# wisp-6-afe.net
KiCad netlist of a schematic drawn in Altium Designer
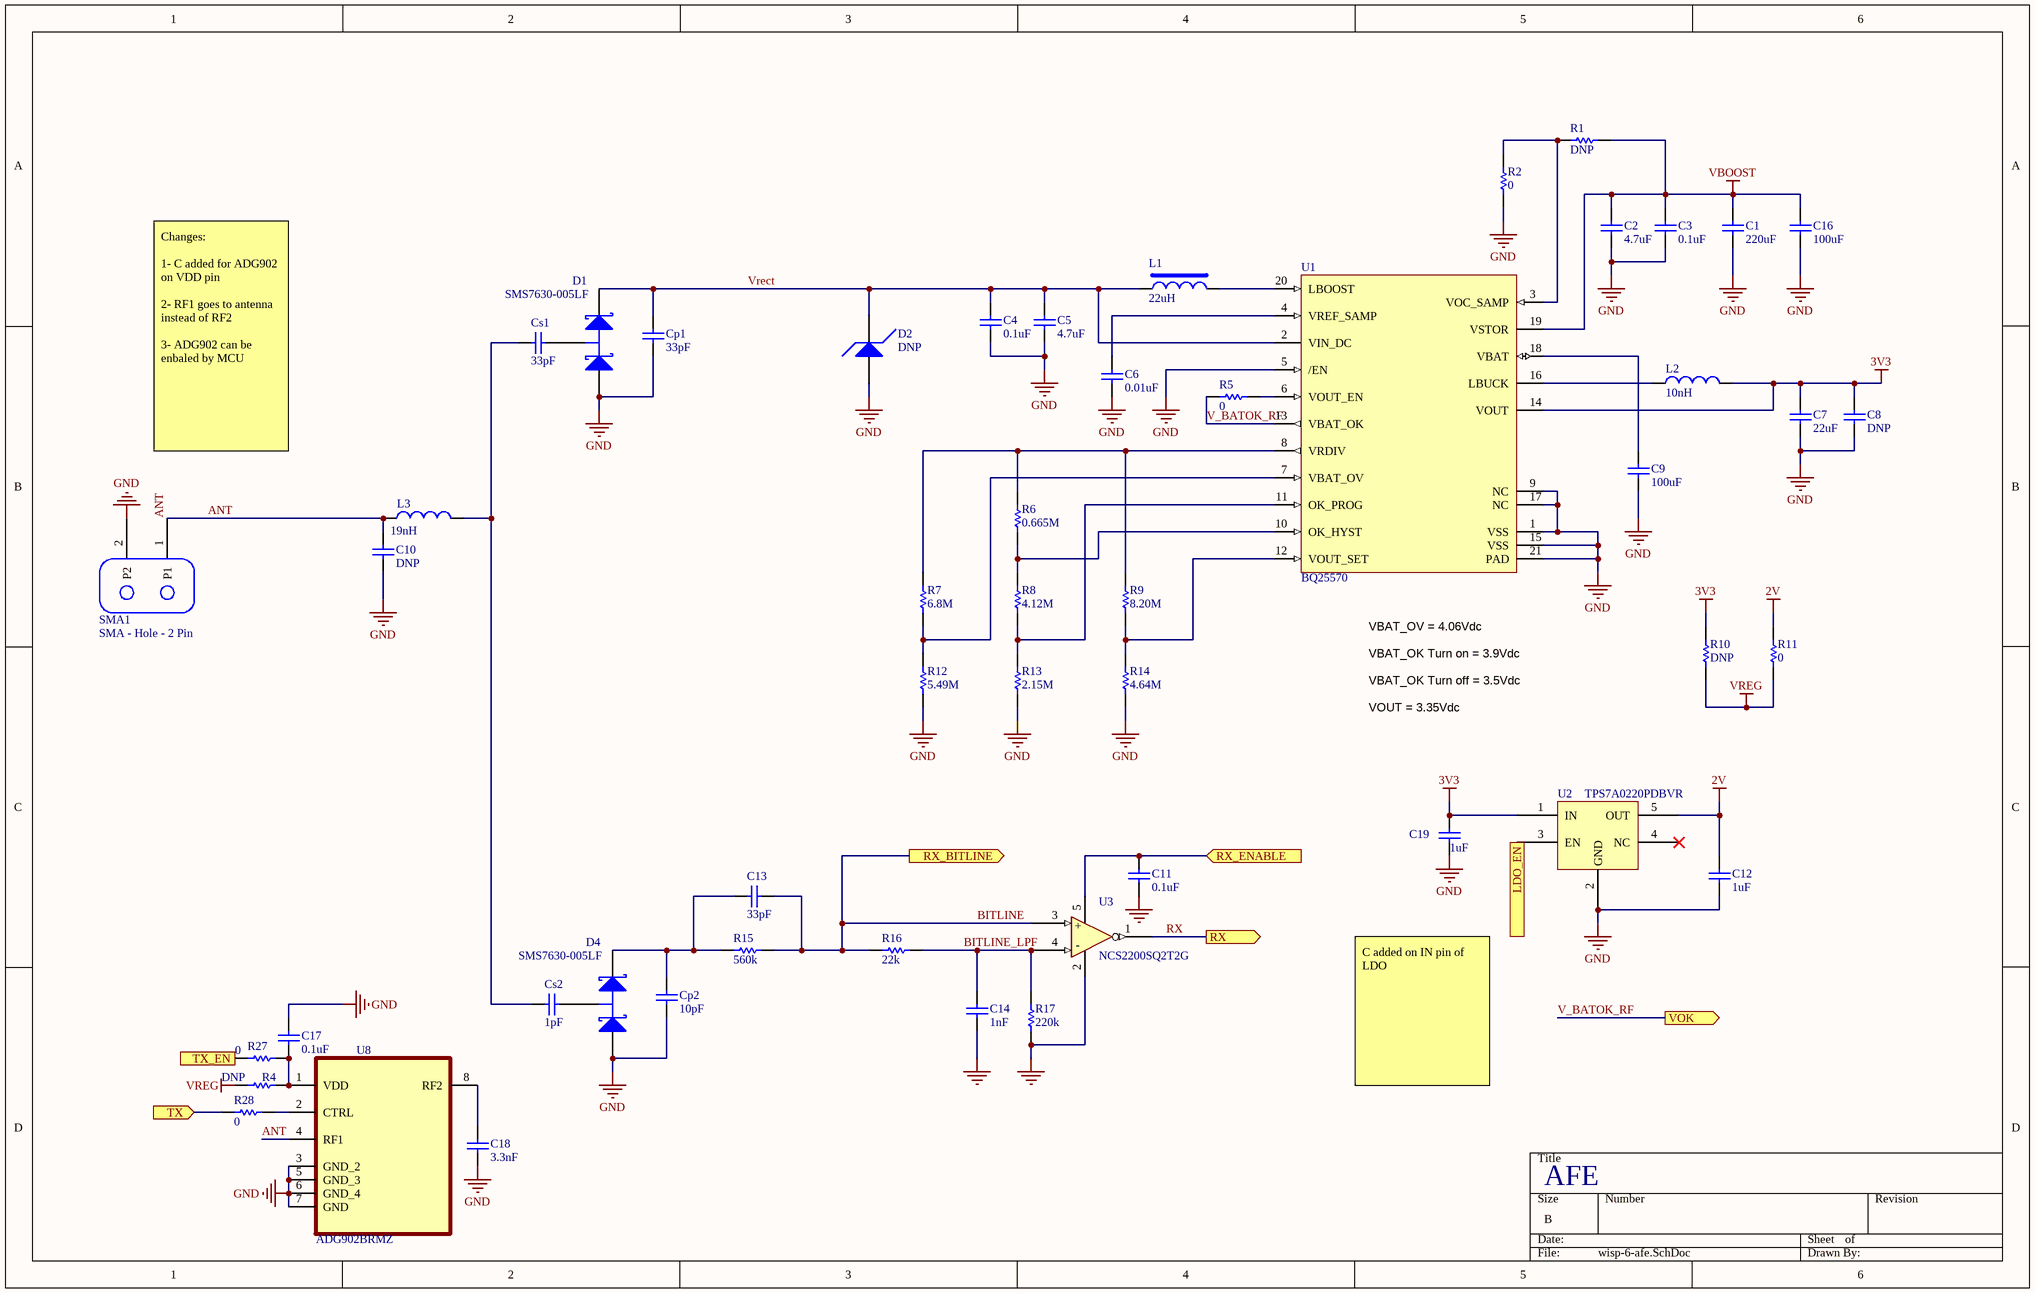
[diagram p0: wisp-6-afe.SchDoc]

(export (version "E")
  (design (tool "Eeschema 10.0.6"))
  (components
    (comp (ref "C1")
      (value "220uF")
      (footprint "1206")
      (description "Ceramic Capacitor (Surface Mount)")
      (fields (field (name "MANUFACTURER") "Generic Ceramic Chip Cap (TBD)") (field (name "Comment") "Cap"))
      (libsource (lib "WISP_AD10") (part "Cap"))
    )
    (comp (ref "C2")
      (value "4.7uF")
      (footprint "0402")
      (description "Ceramic Capacitor (Surface Mount)")
      (fields (field (name "MANUFACTURER") "Generic Ceramic Chip Cap (TBD)") (field (name "Comment") "Cap"))
      (libsource (lib "WISP_AD10") (part "Cap"))
    )
    (comp (ref "C3")
      (value "0.1uF")
      (footprint "0402")
      (description "Ceramic Capacitor (Surface Mount)")
      (fields (field (name "MANUFACTURER") "Generic Ceramic Chip Cap (TBD)") (field (name "Comment") "Cap"))
      (libsource (lib "WISP_AD10") (part "Cap"))
    )
    (comp (ref "C4")
      (value "0.1uF")
      (footprint "0402")
      (description "Ceramic Capacitor (Surface Mount)")
      (fields (field (name "MANUFACTURER") "Generic Ceramic Chip Cap (TBD)") (field (name "Comment") "Cap"))
      (libsource (lib "WISP_AD10") (part "Cap"))
    )
    (comp (ref "C5")
      (value "4.7uF")
      (footprint "0402")
      (description "Ceramic Capacitor (Surface Mount)")
      (fields (field (name "MANUFACTURER") "Generic Ceramic Chip Cap (TBD)") (field (name "Comment") "Cap"))
      (libsource (lib "WISP_AD10") (part "Cap"))
    )
    (comp (ref "C6")
      (value "0.01uF")
      (footprint "0402")
      (description "Ceramic Capacitor (Surface Mount)")
      (fields (field (name "MANUFACTURER") "Generic Ceramic Chip Cap (TBD)") (field (name "Comment") "Cap"))
      (libsource (lib "WISP_AD10") (part "Cap"))
    )
    (comp (ref "C7")
      (value "22uF")
      (footprint "0402")
      (description "Ceramic Capacitor (Surface Mount)")
      (fields (field (name "MANUFACTURER") "Generic Ceramic Chip Cap (TBD)") (field (name "Comment") "Cout1"))
      (libsource (lib "WISP_AD10") (part "Cap"))
    )
    (comp (ref "C8")
      (value "DNP")
      (footprint "0402")
      (description "Ceramic Capacitor (Surface Mount)")
      (fields (field (name "MANUFACTURER") "Generic Ceramic Chip Cap (TBD)") (field (name "Comment") "Cout2"))
      (libsource (lib "WISP_AD10") (part "Cap"))
    )
    (comp (ref "C9")
      (value "100uF")
      (footprint "0805")
      (description "Ceramic Capacitor (Surface Mount)")
      (fields (field (name "MANUFACTURER") "Generic Ceramic Chip Cap (TBD)") (field (name "Comment") "Cap"))
      (libsource (lib "WISP_AD10") (part "Cap"))
    )
    (comp (ref "C10")
      (value "DNP")
      (footprint "0402")
      (description "Ceramic Capacitor (Surface Mount)")
      (fields (field (name "MANUFACTURER") "Generic Ceramic Chip Cap (TBD)") (field (name "Comment") "Cap"))
      (libsource (lib "WISP_AD10") (part "Cap"))
    )
    (comp (ref "C11")
      (value "0.1uF")
      (footprint "0402")
      (description "Ceramic Capacitor (Surface Mount)")
      (fields (field (name "MANUFACTURER") "Generic Ceramic Chip Cap (TBD)") (field (name "Comment") "Cap"))
      (libsource (lib "WISP_AD10") (part "Cap"))
    )
    (comp (ref "C12")
      (value "1uF")
      (footprint "0402")
      (description "Ceramic Capacitor (Surface Mount)")
      (fields (field (name "MANUFACTURER") "Generic Ceramic Chip Cap (TBD)") (field (name "Comment") "Cap"))
      (libsource (lib "WISP_AD10") (part "Cap"))
    )
    (comp (ref "C13")
      (value "33pF")
      (footprint "0402")
      (description "Ceramic Capacitor (Surface Mount)")
      (fields (field (name "MANUFACTURER") "Generic Ceramic Chip Cap (TBD)") (field (name "Comment") "Cap"))
      (libsource (lib "WISP_AD10") (part "Cap"))
    )
    (comp (ref "C14")
      (value "1nF")
      (footprint "0402")
      (description "Ceramic Capacitor (Surface Mount)")
      (fields (field (name "MANUFACTURER") "Generic Ceramic Chip Cap (TBD)") (field (name "Comment") "Cap"))
      (libsource (lib "WISP_AD10") (part "Cap"))
    )
    (comp (ref "C16")
      (value "100uF")
      (footprint "0805")
      (description "Ceramic Capacitor (Surface Mount)")
      (fields (field (name "MANUFACTURER") "Generic Ceramic Chip Cap (TBD)") (field (name "Comment") "Cap"))
      (libsource (lib "WISP_AD10") (part "Cap"))
    )
    (comp (ref "C17")
      (value "0.1uF")
      (footprint "0402")
      (description "Ceramic Capacitor (Surface Mount)")
      (fields (field (name "MANUFACTURER") "Generic Ceramic Chip Cap (TBD)") (field (name "Comment") "Cap"))
      (libsource (lib "WISP_AD10") (part "Cap"))
    )
    (comp (ref "C18")
      (value "3.3nF")
      (footprint "0402")
      (description "Ceramic Capacitor (Surface Mount)")
      (fields (field (name "MANUFACTURER") "Generic Ceramic Chip Cap (TBD)") (field (name "Comment") "Cap"))
      (libsource (lib "WISP_AD10") (part "Cap"))
    )
    (comp (ref "C19")
      (value "1uF")
      (footprint "0402")
      (description "Ceramic Capacitor (Surface Mount)")
      (fields (field (name "MANUFACTURER") "Generic Ceramic Chip Cap (TBD)") (field (name "Comment") "Cap"))
      (libsource (lib "WISP_AD10") (part "Cap"))
    )
    (comp (ref "Cp1")
      (value "33pF")
      (footprint "0402")
      (description "Ceramic Capacitor (Surface Mount)")
      (fields (field (name "MANUFACTURER") "Generic Ceramic Chip Cap (TBD)") (field (name "Comment") "Cap"))
      (libsource (lib "WISP_AD10") (part "Cap"))
    )
    (comp (ref "Cp2")
      (value "10pF")
      (footprint "0402")
      (description "Ceramic Capacitor (Surface Mount)")
      (fields (field (name "MANUFACTURER") "Generic Ceramic Chip Cap (TBD)") (field (name "Comment") "Cap"))
      (libsource (lib "WISP_AD10") (part "Cap"))
    )
    (comp (ref "Cs1")
      (value "33pF")
      (footprint "0402")
      (description "Ceramic Capacitor (Surface Mount)")
      (fields (field (name "MANUFACTURER") "Generic Ceramic Chip Cap (TBD)") (field (name "Comment") "Cap"))
      (libsource (lib "WISP_AD10") (part "Cap"))
    )
    (comp (ref "Cs2")
      (value "1pF")
      (footprint "0402")
      (description "Ceramic Capacitor (Surface Mount)")
      (fields (field (name "MANUFACTURER") "Generic Ceramic Chip Cap (TBD)") (field (name "Comment") "Cap"))
      (libsource (lib "WISP_AD10") (part "Cap"))
    )
    (comp (ref "D1")
      (value "SMS7630-005LF")
      (footprint "WISP_AD10:SOT23 - N")
      (description "Schottky Diodes & Rectifiers Ls=1.5nH SOT-23 Series Pair")
      (libsource (lib "WISP_AD10") (part "SMS7630-005LF"))
    )
    (comp (ref "D2")
      (value "DNP")
      (footprint "Zener_SOD-523")
      (description "Diode - Zener")
      (libsource (lib "WISP_AD10") (part "Zener_SOD-523"))
    )
    (comp (ref "D4")
      (value "SMS7630-005LF")
      (footprint "WISP_AD10:SOT23 - N")
      (description "Schottky Diodes & Rectifiers Ls=1.5nH SOT-23 Series Pair")
      (libsource (lib "WISP_AD10") (part "SMS7630-005LF"))
    )
    (comp (ref "L1")
      (value "22uH")
      (footprint "LPS4018")
      (description "Inductor (Surface Mount)")
      (fields (field (name "MANUFACTURER") "Coil Craft") (field (name "Comment") "Ind_LPS4018"))
      (libsource (lib "WISP_AD10") (part "Ind_LPS4018"))
    )
    (comp (ref "L2")
      (value "10nH")
      (footprint "IND1008")
      (description "Inductor (Surface Mount)")
      (fields (field (name "Comment") "Ind"))
      (libsource (lib "WISP_AD10") (part "Ind"))
    )
    (comp (ref "L3")
      (value "19nH")
      (footprint "0603")
      (description "Inductor (Surface Mount)")
      (fields (field (name "Comment") "Ind"))
      (libsource (lib "WISP_AD10") (part "Ind"))
    )
    (comp (ref "R1")
      (value "DNP")
      (footprint "0402")
      (description "Chip Resistor (Surface Mount)")
      (fields (field (name "MANUFACTURER") "Generic Chip Res (TBD)") (field (name "Comment") "R_80%"))
      (libsource (lib "WISP_AD10") (part "Res"))
    )
    (comp (ref "R2")
      (value "0")
      (footprint "0402")
      (description "Chip Resistor (Surface Mount)")
      (fields (field (name "MANUFACTURER") "Generic Chip Res (TBD)") (field (name "Comment") "R_50%"))
      (libsource (lib "WISP_AD10") (part "Res"))
    )
    (comp (ref "R4")
      (value "DNP")
      (footprint "0402")
      (description "Chip Resistor (Surface Mount)")
      (fields (field (name "MANUFACTURER") "Generic Chip Res (TBD)") (field (name "Comment") "Rok3"))
      (libsource (lib "WISP_AD10") (part "Res"))
    )
    (comp (ref "R5")
      (value "0")
      (footprint "0402")
      (description "Chip Resistor (Surface Mount)")
      (fields (field (name "MANUFACTURER") "Generic Chip Res (TBD)") (field (name "Comment") "R_VBAT_OK"))
      (libsource (lib "WISP_AD10") (part "Res"))
    )
    (comp (ref "R6")
      (value "0.665M")
      (footprint "0402")
      (description "Chip Resistor (Surface Mount)")
      (fields (field (name "MANUFACTURER") "Generic Chip Res (TBD)") (field (name "Comment") "Rok3"))
      (libsource (lib "WISP_AD10") (part "Res"))
    )
    (comp (ref "R7")
      (value "6.8M")
      (footprint "0402")
      (description "Chip Resistor (Surface Mount)")
      (fields (field (name "MANUFACTURER") "Generic Chip Res (TBD)") (field (name "Comment") "Rov2"))
      (libsource (lib "WISP_AD10") (part "Res"))
    )
    (comp (ref "R8")
      (value "4.12M")
      (footprint "0402")
      (description "Chip Resistor (Surface Mount)")
      (fields (field (name "MANUFACTURER") "Generic Chip Res (TBD)") (field (name "Comment") "Rok2"))
      (libsource (lib "WISP_AD10") (part "Res"))
    )
    (comp (ref "R9")
      (value "8.20M")
      (footprint "0402")
      (description "Chip Resistor (Surface Mount)")
      (fields (field (name "MANUFACTURER") "Generic Chip Res (TBD)") (field (name "Comment") "8.2M"))
      (libsource (lib "WISP_AD10") (part "Res"))
    )
    (comp (ref "R10")
      (value "DNP")
      (footprint "0402")
      (description "Chip Resistor (Surface Mount)")
      (fields (field (name "MANUFACTURER") "Generic Chip Res (TBD)") (field (name "Comment") "Res"))
      (libsource (lib "WISP_AD10") (part "Res"))
    )
    (comp (ref "R11")
      (value "0")
      (footprint "0402")
      (description "Chip Resistor (Surface Mount)")
      (fields (field (name "MANUFACTURER") "Generic Chip Res (TBD)") (field (name "Comment") "Res"))
      (libsource (lib "WISP_AD10") (part "Res"))
    )
    (comp (ref "R12")
      (value "5.49M")
      (footprint "0402")
      (description "Chip Resistor (Surface Mount)")
      (fields (field (name "MANUFACTURER") "Generic Chip Res (TBD)") (field (name "Comment") "Rov1"))
      (libsource (lib "WISP_AD10") (part "Res"))
    )
    (comp (ref "R13")
      (value "2.15M")
      (footprint "0402")
      (description "Chip Resistor (Surface Mount)")
      (fields (field (name "MANUFACTURER") "Generic Chip Res (TBD)") (field (name "Comment") "Rok1"))
      (libsource (lib "WISP_AD10") (part "Res"))
    )
    (comp (ref "R14")
      (value "4.64M")
      (footprint "0402")
      (description "Chip Resistor (Surface Mount)")
      (fields (field (name "MANUFACTURER") "Generic Chip Res (TBD)"))
      (libsource (lib "WISP_AD10") (part "Res"))
    )
    (comp (ref "R15")
      (value "560k")
      (footprint "0402")
      (description "Chip Resistor (Surface Mount)")
      (fields (field (name "MANUFACTURER") "Generic Chip Res (TBD)") (field (name "Comment") "Res"))
      (libsource (lib "WISP_AD10") (part "Res"))
    )
    (comp (ref "R16")
      (value "22k")
      (footprint "0402")
      (description "Chip Resistor (Surface Mount)")
      (fields (field (name "MANUFACTURER") "Generic Chip Res (TBD)") (field (name "Comment") "Res"))
      (libsource (lib "WISP_AD10") (part "Res"))
    )
    (comp (ref "R17")
      (value "220k")
      (footprint "0402")
      (description "Chip Resistor (Surface Mount)")
      (fields (field (name "MANUFACTURER") "Generic Chip Res (TBD)") (field (name "Comment") "Res"))
      (libsource (lib "WISP_AD10") (part "Res"))
    )
    (comp (ref "R27")
      (value "0")
      (footprint "0402")
      (description "Chip Resistor (Surface Mount)")
      (fields (field (name "MANUFACTURER") "Generic Chip Res (TBD)") (field (name "Comment") "Rok3"))
      (libsource (lib "WISP_AD10") (part "Res"))
    )
    (comp (ref "R28")
      (value "0")
      (footprint "0402")
      (description "Chip Resistor (Surface Mount)")
      (fields (field (name "MANUFACTURER") "Generic Chip Res (TBD)") (field (name "Comment") "Rok3"))
      (libsource (lib "WISP_AD10") (part "Res"))
    )
    (comp (ref "SMA1")
      (value "SMA - Hole - 2 Pin")
      (footprint "SMA - Hole - 2 Pin")
      (description "Two pin SMA connector wisp")
      (libsource (lib "WISP_AD10") (part "SMA - Hole - 2 Pin"))
    )
    (comp (ref "U1")
      (value "BQ25570")
      (footprint "BQ25570")
      (description "Boost Charger")
      (fields
        (field (name "DIGI-KEY PART NUMBER") "296-37014-1-ND")
        (field (name "MANUFACTURER") "Texas Instruments")
      )
      (libsource (lib "WISP_AD10") (part "BQ25570"))
    )
    (comp (ref "U2")
      (value "TPS7A0220PDBVR")
      (footprint "SOT23-5")
      (description "IC REG LINEAR 2V 200MA SOT23-5")
      (libsource (lib "WISP_AD10") (part "TPS7A0218PDBVR"))
    )
    (comp (ref "U3")
      (value "NCS2200SQ2T2G")
      (footprint "SC70-5")
      (description "Comparator General Purpose Open Drain SC-70-5")
      (fields
        (field (name "DIGI-KEY PART NUMBER") "NCS2200SQ2T2GOSTR-ND")
        (field (name "MANUFACTURER") "ON Semiconductor")
      )
      (libsource (lib "WISP_AD10") (part "NCS2200"))
    )
    (comp (ref "U8")
      (value "ADG902BRMZ")
      (footprint "SOP65P490X110-8N")
      (description "RF Switch IC General Purpose SPST 2.5GHz 50Ohm 8-MSOP")
      (fields (field (name "MF") "Analog Devices") (field (name "DIGI-KEY_PART_NUMBER") "ADG902BRMZ-ND"))
      (libsource (lib "ADG902BRMZ") (part "ADG902BRMZ"))
    )
  )
  (nets
    (net (code "1") (name "/ANT") (class "Default")
      (node (ref "C10") (pin "2") (pinfunction "2_2") (pintype "passive"))
      (node (ref "L3") (pin "1") (pinfunction "1_1") (pintype "passive"))
      (node (ref "SMA1") (pin "1") (pinfunction "P1_1") (pintype "passive"))
      (node (ref "U8") (pin "4") (pinfunction "RF1_4") (pintype "passive"))
    )
    (net (code "2") (name "/BITLINE") (class "Default")
      (node (ref "C13") (pin "2") (pinfunction "2_2") (pintype "passive"))
      (node (ref "R15") (pin "1") (pinfunction "1_1") (pintype "passive"))
      (node (ref "R16") (pin "2") (pinfunction "2_2") (pintype "passive"))
      (node (ref "U3") (pin "3") (pinfunction "IN+_3") (pintype "input"))
    )
    (net (code "3") (name "/BITLINE_LPF") (class "Default")
      (node (ref "C14") (pin "1") (pinfunction "1_1") (pintype "passive"))
      (node (ref "R16") (pin "1") (pinfunction "1_1") (pintype "passive"))
      (node (ref "R17") (pin "1") (pinfunction "1_1") (pintype "passive"))
      (node (ref "U3") (pin "4") (pinfunction "In-_4") (pintype "input"))
    )
    (net (code "4") (name "/LDO_EN") (class "Default")
      (node (ref "U2") (pin "3") (pinfunction "EN_3") (pintype "passive"))
    )
    (net (code "5") (name "/RX") (class "Default")
      (node (ref "U3") (pin "1") (pinfunction "OUT_1") (pintype "output"))
    )
    (net (code "6") (name "/RX_ENABLE") (class "Default")
      (node (ref "C11") (pin "1") (pinfunction "1_1") (pintype "passive"))
      (node (ref "U3") (pin "5") (pinfunction "VDD_5") (pintype "passive"))
    )
    (net (code "7") (name "/TX") (class "Default")
      (node (ref "R28") (pin "2") (pinfunction "2_2") (pintype "passive"))
    )
    (net (code "8") (name "/TX_EN") (class "Default")
      (node (ref "R27") (pin "2") (pinfunction "2_2") (pintype "passive"))
    )
    (net (code "9") (name "/V_BATOK_RF") (class "Default")
      (node (ref "R5") (pin "1") (pinfunction "1_1") (pintype "passive"))
      (node (ref "U1") (pin "13") (pinfunction "VBAT_OK_13") (pintype "output"))
    )
    (net (code "10") (name "/Vrect") (class "Default")
      (node (ref "C4") (pin "2") (pinfunction "2_2") (pintype "passive"))
      (node (ref "C5") (pin "2") (pinfunction "2_2") (pintype "passive"))
      (node (ref "Cp1") (pin "1") (pinfunction "1_1") (pintype "passive"))
      (node (ref "D1") (pin "2") (pinfunction "K_2") (pintype "passive"))
      (node (ref "D2") (pin "2") (pinfunction "K_2") (pintype "passive"))
      (node (ref "L1") (pin "1") (pinfunction "1_1") (pintype "passive"))
      (node (ref "U1") (pin "2") (pinfunction "VIN_DC_2") (pintype "passive"))
    )
    (net (code "11") (name "2V") (class "Default")
      (node (ref "C12") (pin "2") (pinfunction "2_2") (pintype "passive"))
      (node (ref "R11") (pin "1") (pinfunction "1_1") (pintype "passive"))
      (node (ref "U2") (pin "5") (pinfunction "OUT_5") (pintype "passive"))
    )
    (net (code "12") (name "3V3") (class "Default")
      (node (ref "C19") (pin "2") (pinfunction "2_2") (pintype "passive"))
      (node (ref "C7") (pin "2") (pinfunction "2_2") (pintype "passive"))
      (node (ref "C8") (pin "2") (pinfunction "2_2") (pintype "passive"))
      (node (ref "L2") (pin "2") (pinfunction "2_2") (pintype "passive"))
      (node (ref "R10") (pin "1") (pinfunction "1_1") (pintype "passive"))
      (node (ref "U1") (pin "14") (pinfunction "VOUT_14") (pintype "passive"))
      (node (ref "U2") (pin "1") (pinfunction "IN_1") (pintype "passive"))
    )
    (net (code "13") (name "GND") (class "Default")
      (node (ref "C1") (pin "1") (pinfunction "1_1") (pintype "passive"))
      (node (ref "C10") (pin "1") (pinfunction "1_1") (pintype "passive"))
      (node (ref "C11") (pin "2") (pinfunction "2_2") (pintype "passive"))
      (node (ref "C12") (pin "1") (pinfunction "1_1") (pintype "passive"))
      (node (ref "C14") (pin "2") (pinfunction "2_2") (pintype "passive"))
      (node (ref "C16") (pin "1") (pinfunction "1_1") (pintype "passive"))
      (node (ref "C17") (pin "1") (pinfunction "1_1") (pintype "passive"))
      (node (ref "C18") (pin "1") (pinfunction "1_1") (pintype "passive"))
      (node (ref "C19") (pin "1") (pinfunction "1_1") (pintype "passive"))
      (node (ref "C2") (pin "1") (pinfunction "1_1") (pintype "passive"))
      (node (ref "C3") (pin "1") (pinfunction "1_1") (pintype "passive"))
      (node (ref "C4") (pin "1") (pinfunction "1_1") (pintype "passive"))
      (node (ref "C5") (pin "1") (pinfunction "1_1") (pintype "passive"))
      (node (ref "C6") (pin "1") (pinfunction "1_1") (pintype "passive"))
      (node (ref "C7") (pin "1") (pinfunction "1_1") (pintype "passive"))
      (node (ref "C8") (pin "1") (pinfunction "1_1") (pintype "passive"))
      (node (ref "C9") (pin "1") (pinfunction "1_1") (pintype "passive"))
      (node (ref "Cp1") (pin "2") (pinfunction "2_2") (pintype "passive"))
      (node (ref "Cp2") (pin "2") (pinfunction "2_2") (pintype "passive"))
      (node (ref "D1") (pin "1") (pinfunction "A_1") (pintype "passive"))
      (node (ref "D2") (pin "1") (pinfunction "A_1") (pintype "passive"))
      (node (ref "D4") (pin "1") (pinfunction "A_1") (pintype "passive"))
      (node (ref "R12") (pin "2") (pinfunction "2_2") (pintype "passive"))
      (node (ref "R13") (pin "2") (pinfunction "2_2") (pintype "passive"))
      (node (ref "R14") (pin "2") (pinfunction "2_2") (pintype "passive"))
      (node (ref "R17") (pin "2") (pinfunction "2_2") (pintype "passive"))
      (node (ref "R2") (pin "1") (pinfunction "1_1") (pintype "passive"))
      (node (ref "SMA1") (pin "2") (pinfunction "P2_2") (pintype "passive"))
      (node (ref "U1") (pin "1") (pinfunction "VSS_1") (pintype "passive"))
      (node (ref "U1") (pin "15") (pinfunction "VSS_15") (pintype "passive"))
      (node (ref "U1") (pin "17") (pinfunction "NC_17") (pintype "passive"))
      (node (ref "U1") (pin "21") (pinfunction "PAD_21") (pintype "passive"))
      (node (ref "U1") (pin "5") (pinfunction "/EN_5") (pintype "input"))
      (node (ref "U1") (pin "9") (pinfunction "NC_9") (pintype "passive"))
      (node (ref "U2") (pin "2") (pinfunction "GND_2") (pintype "passive"))
      (node (ref "U3") (pin "2") (pinfunction "Gnd_2") (pintype "power_in"))
      (node (ref "U8") (pin "3") (pinfunction "GND_2_3") (pintype "passive"))
      (node (ref "U8") (pin "5") (pinfunction "GND_3_5") (pintype "passive"))
      (node (ref "U8") (pin "6") (pinfunction "GND_4_6") (pintype "passive"))
      (node (ref "U8") (pin "7") (pinfunction "GND_7") (pintype "passive"))
    )
    (net (code "14") (name "Net-(Cs1-Pad1)") (class "Default")
      (node (ref "Cs1") (pin "1") (pinfunction "1_1") (pintype "passive"))
      (node (ref "Cs2") (pin "1") (pinfunction "1_1") (pintype "passive"))
      (node (ref "L3") (pin "2") (pinfunction "2_2") (pintype "passive"))
    )
    (net (code "15") (name "Net-(D1-C)") (class "Default")
      (node (ref "Cs1") (pin "2") (pinfunction "2_2") (pintype "passive"))
      (node (ref "D1") (pin "3") (pinfunction "C_3") (pintype "passive"))
    )
    (net (code "16") (name "Net-(D4-C)") (class "Default")
      (node (ref "Cs2") (pin "2") (pinfunction "2_2") (pintype "passive"))
      (node (ref "D4") (pin "3") (pinfunction "C_3") (pintype "passive"))
    )
    (net (code "17") (name "Net-(D4-K)") (class "Default")
      (node (ref "C13") (pin "1") (pinfunction "1_1") (pintype "passive"))
      (node (ref "Cp2") (pin "1") (pinfunction "1_1") (pintype "passive"))
      (node (ref "D4") (pin "2") (pinfunction "K_2") (pintype "passive"))
      (node (ref "R15") (pin "2") (pinfunction "2_2") (pintype "passive"))
    )
    (net (code "18") (name "Net-(U1-LBOOST)") (class "Default")
      (node (ref "L1") (pin "2") (pinfunction "2_2") (pintype "passive"))
      (node (ref "U1") (pin "20") (pinfunction "LBOOST_20") (pintype "input"))
    )
    (net (code "19") (name "Net-(U1-LBUCK)") (class "Default")
      (node (ref "L2") (pin "1") (pinfunction "1_1") (pintype "passive"))
      (node (ref "U1") (pin "16") (pinfunction "LBUCK_16") (pintype "passive"))
    )
    (net (code "20") (name "Net-(U1-OK_HYST)") (class "Default")
      (node (ref "R6") (pin "2") (pinfunction "2_2") (pintype "passive"))
      (node (ref "R8") (pin "1") (pinfunction "1_1") (pintype "passive"))
      (node (ref "U1") (pin "10") (pinfunction "OK_HYST_10") (pintype "input"))
    )
    (net (code "21") (name "Net-(U1-OK_PROG)") (class "Default")
      (node (ref "R13") (pin "1") (pinfunction "1_1") (pintype "passive"))
      (node (ref "R8") (pin "2") (pinfunction "2_2") (pintype "passive"))
      (node (ref "U1") (pin "11") (pinfunction "OK_PROG_11") (pintype "input"))
    )
    (net (code "22") (name "Net-(U1-VBAT)") (class "Default")
      (node (ref "C9") (pin "2") (pinfunction "2_2") (pintype "passive"))
      (node (ref "U1") (pin "18") (pinfunction "VBAT_18") (pintype "bidirectional"))
    )
    (net (code "23") (name "Net-(U1-VBAT_OV)") (class "Default")
      (node (ref "R12") (pin "1") (pinfunction "1_1") (pintype "passive"))
      (node (ref "R7") (pin "2") (pinfunction "2_2") (pintype "passive"))
      (node (ref "U1") (pin "7") (pinfunction "VBAT_OV_7") (pintype "input"))
    )
    (net (code "24") (name "Net-(U1-VOC_SAMP)") (class "Default")
      (node (ref "R1") (pin "1") (pinfunction "1_1") (pintype "passive"))
      (node (ref "R2") (pin "2") (pinfunction "2_2") (pintype "passive"))
      (node (ref "U1") (pin "3") (pinfunction "VOC_SAMP_3") (pintype "input"))
    )
    (net (code "25") (name "Net-(U1-VOUT_EN)") (class "Default")
      (node (ref "R5") (pin "2") (pinfunction "2_2") (pintype "passive"))
      (node (ref "U1") (pin "6") (pinfunction "VOUT_EN_6") (pintype "input"))
    )
    (net (code "26") (name "Net-(U1-VOUT_SET)") (class "Default")
      (node (ref "R14") (pin "1") (pinfunction "1_1") (pintype "passive"))
      (node (ref "R9") (pin "2") (pinfunction "2_2") (pintype "passive"))
      (node (ref "U1") (pin "12") (pinfunction "VOUT_SET_12") (pintype "input"))
    )
    (net (code "27") (name "Net-(U1-VRDIV)") (class "Default")
      (node (ref "R6") (pin "1") (pinfunction "1_1") (pintype "passive"))
      (node (ref "R7") (pin "1") (pinfunction "1_1") (pintype "passive"))
      (node (ref "R9") (pin "1") (pinfunction "1_1") (pintype "passive"))
      (node (ref "U1") (pin "8") (pinfunction "VRDIV_8") (pintype "output"))
    )
    (net (code "28") (name "Net-(U1-VREF_SAMP)") (class "Default")
      (node (ref "C6") (pin "2") (pinfunction "2_2") (pintype "passive"))
      (node (ref "U1") (pin "4") (pinfunction "VREF_SAMP_4") (pintype "input"))
    )
    (net (code "29") (name "Net-(U8-CTRL)") (class "Default")
      (node (ref "R28") (pin "1") (pinfunction "1_1") (pintype "passive"))
      (node (ref "U8") (pin "2") (pinfunction "CTRL_2") (pintype "passive"))
    )
    (net (code "30") (name "Net-(U8-RF2)") (class "Default")
      (node (ref "C18") (pin "2") (pinfunction "2_2") (pintype "passive"))
      (node (ref "U8") (pin "8") (pinfunction "RF2_8") (pintype "passive"))
    )
    (net (code "31") (name "Net-(U8-VDD)") (class "Default")
      (node (ref "C17") (pin "2") (pinfunction "2_2") (pintype "passive"))
      (node (ref "R27") (pin "1") (pinfunction "1_1") (pintype "passive"))
      (node (ref "R4") (pin "1") (pinfunction "1_1") (pintype "passive"))
      (node (ref "U8") (pin "1") (pinfunction "VDD_1") (pintype "power_in"))
    )
    (net (code "32") (name "VBOOST") (class "Default")
      (node (ref "C1") (pin "2") (pinfunction "2_2") (pintype "passive"))
      (node (ref "C16") (pin "2") (pinfunction "2_2") (pintype "passive"))
      (node (ref "C2") (pin "2") (pinfunction "2_2") (pintype "passive"))
      (node (ref "C3") (pin "2") (pinfunction "2_2") (pintype "passive"))
      (node (ref "R1") (pin "2") (pinfunction "2_2") (pintype "passive"))
      (node (ref "U1") (pin "19") (pinfunction "VSTOR_19") (pintype "passive"))
    )
    (net (code "33") (name "VREG") (class "Default")
      (node (ref "R10") (pin "2") (pinfunction "2_2") (pintype "passive"))
      (node (ref "R11") (pin "2") (pinfunction "2_2") (pintype "passive"))
      (node (ref "R4") (pin "2") (pinfunction "2_2") (pintype "passive"))
    )
    (net (code "34") (name "unconnected-(U2-NC-Pad4)") (class "Default")
      (node (ref "U2") (pin "4") (pinfunction "NC_4") (pintype "passive+no_connect"))
    )
  )
)
